# 08_SOM_USB_CARD.net
KiCad netlist of a schematic drawn in Altium Designer
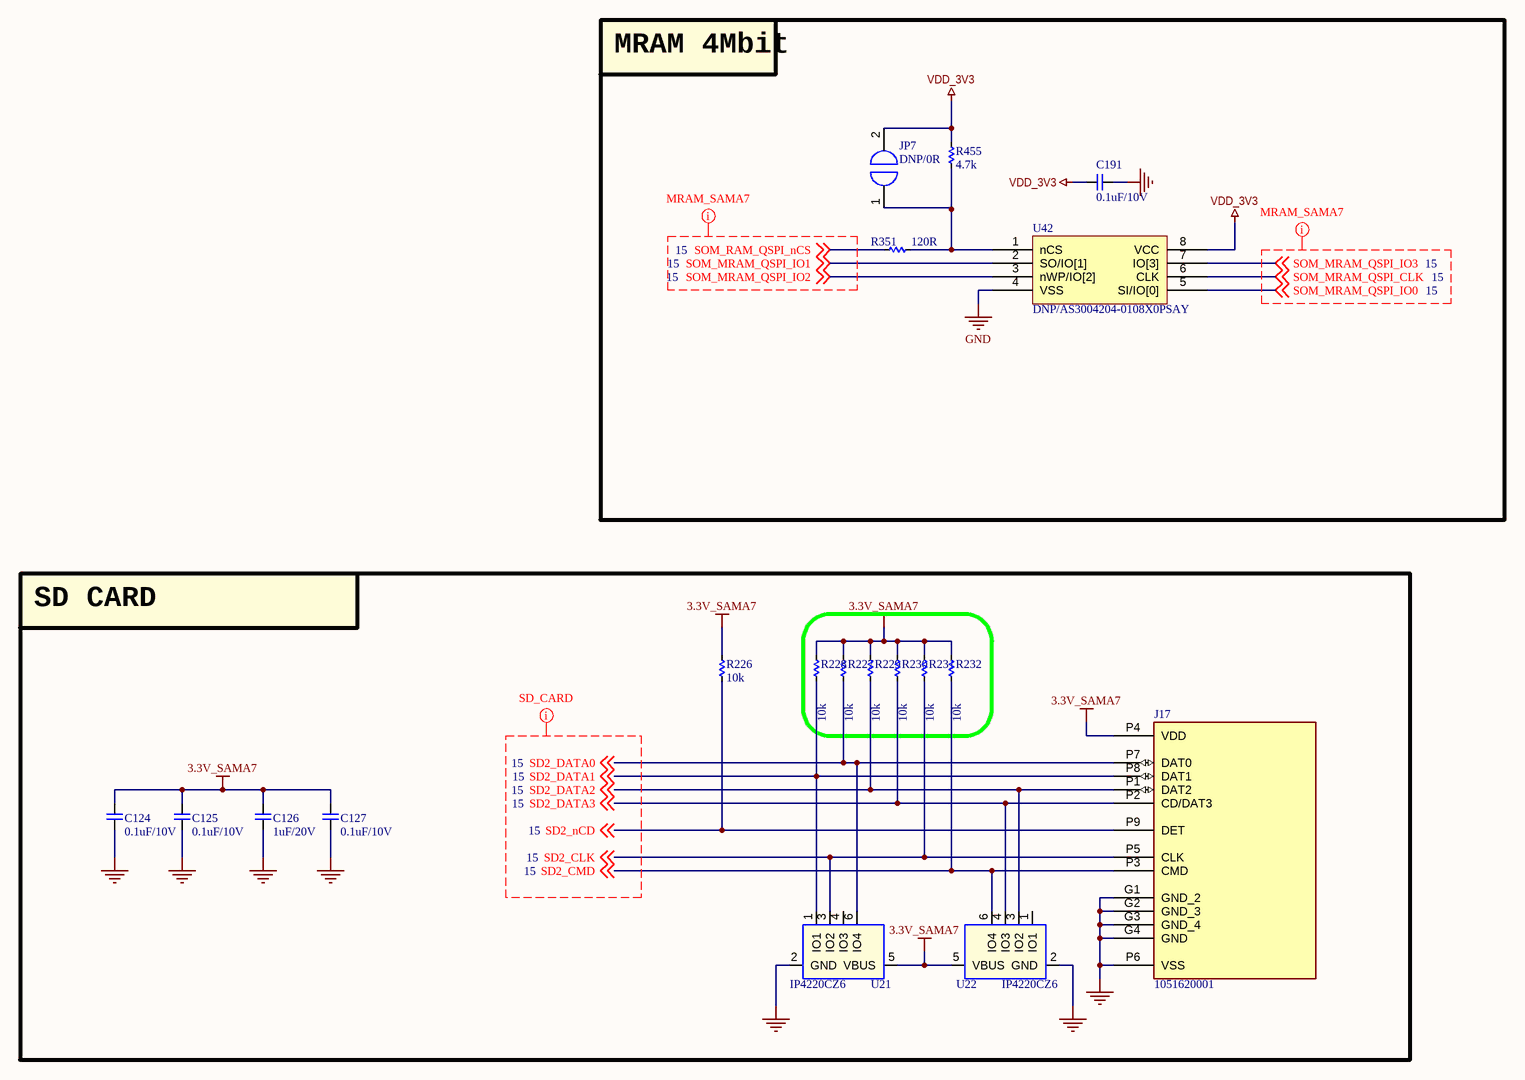
[diagram p0: 08_SOM_USB_CARD.SchDoc]

(export (version "E")
  (design (tool "Eeschema 10.0.6"))
  (components
    (comp (ref "C124")
      (value "0.1uF/10V")
      (footprint "CAP_C_1005X60")
      (description "CAP")
      (libsource (lib "LABLIB") (part "_CAP_C_2"))
    )
    (comp (ref "C125")
      (value "0.1uF/10V")
      (footprint "CAP_C_1005X60")
      (description "CAP")
      (libsource (lib "LABLIB") (part "_CAP_C_2"))
    )
    (comp (ref "C126")
      (value "1uF/20V")
      (footprint "CAP_C_1005X60")
      (description "CAP")
      (libsource (lib "LABLIB") (part "_CAP_C_2"))
    )
    (comp (ref "C127")
      (value "0.1uF/10V")
      (footprint "CAP_C_1005X60")
      (description "CAP")
      (libsource (lib "LABLIB") (part "_CAP_C_2"))
    )
    (comp (ref "C191")
      (value "0.1uF/10V")
      (footprint "CAP_C_1005X60")
      (description "CAP")
      (libsource (lib "LABLIB") (part "_CAP_C_2"))
    )
    (comp (ref "J17")
      (value "1051620001")
      (footprint "Molex_1051620001")
      (description "9 (8 + 1) Position Card Connector Secure Digital - microSDâ„¢ Surface Mount, Right Angle Gold")
      (fields (field (name "MF") "Molex"))
      (libsource (lib "new_component") (part "Molex_1051620001"))
    )
    (comp (ref "JP7") (value "DNP/0R") (footprint "JUMPER_1608") (libsource (lib "EXP_V1") (part "JUMPER")))
    (comp (ref "R226")
      (value "10k")
      (footprint "RES_C_1005X40")
      (description "RES")
      (libsource (lib "LABLIB") (part "_RES_B_2"))
    )
    (comp (ref "R227")
      (value "10k")
      (footprint "RES_C_1005X40")
      (description "RES")
      (libsource (lib "LABLIB") (part "_RES_B_2"))
    )
    (comp (ref "R228")
      (value "10k")
      (footprint "RES_C_1005X40")
      (description "RES")
      (libsource (lib "LABLIB") (part "_RES_B_2"))
    )
    (comp (ref "R229")
      (value "10k")
      (footprint "RES_C_1005X40")
      (description "RES")
      (libsource (lib "LABLIB") (part "_RES_B_2"))
    )
    (comp (ref "R230")
      (value "10k")
      (footprint "RES_C_1005X40")
      (description "RES")
      (libsource (lib "LABLIB") (part "_RES_B_2"))
    )
    (comp (ref "R231")
      (value "10k")
      (footprint "RES_C_1005X40")
      (description "RES")
      (libsource (lib "LABLIB") (part "_RES_B_2"))
    )
    (comp (ref "R232")
      (value "10k")
      (footprint "RES_C_1005X40")
      (description "RES")
      (libsource (lib "LABLIB") (part "_RES_B_2"))
    )
    (comp (ref "R351")
      (value "120R")
      (footprint "RES_C_1005X40")
      (description "RES")
      (libsource (lib "LABLIB") (part "_RES_B_2"))
    )
    (comp (ref "R455")
      (value "4.7k")
      (footprint "RES_C_1005X40")
      (description "RES")
      (libsource (lib "LABLIB") (part "_RES_B_2"))
    )
    (comp (ref "U21")
      (value "IP4220CZ6")
      (footprint "SOT95P280X145-6N")
      (libsource (lib "LABLIB") (part "IP4220CZ6_0"))
    )
    (comp (ref "U22")
      (value "IP4220CZ6")
      (footprint "SOT95P280X145-6N")
      (libsource (lib "") (part "IP4220CZ6_0_1"))
    )
    (comp (ref "U42")
      (value "DNP/AS3004204-0108X0PSAY")
      (footprint "SOIC127P790X216-8")
      (libsource (lib "LABLIB") (part "IC_RAM_AS3004204-0108X0PSAY"))
    )
  )
  (nets
    (net (code "1") (name "3.3V_SAMA7") (class "Default")
      (node (ref "C124") (pin "2") (pinfunction "2_2") (pintype "passive"))
      (node (ref "C125") (pin "2") (pinfunction "2_2") (pintype "passive"))
      (node (ref "C126") (pin "2") (pinfunction "2_2") (pintype "passive"))
      (node (ref "C127") (pin "2") (pinfunction "2_2") (pintype "passive"))
      (node (ref "J17") (pin "P4") (pinfunction "VDD_P4") (pintype "power_in"))
      (node (ref "R226") (pin "2") (pinfunction "2_2") (pintype "passive"))
      (node (ref "R227") (pin "2") (pinfunction "2_2") (pintype "passive"))
      (node (ref "R228") (pin "2") (pinfunction "2_2") (pintype "passive"))
      (node (ref "R229") (pin "2") (pinfunction "2_2") (pintype "passive"))
      (node (ref "R230") (pin "2") (pinfunction "2_2") (pintype "passive"))
      (node (ref "R231") (pin "2") (pinfunction "2_2") (pintype "passive"))
      (node (ref "R232") (pin "2") (pinfunction "2_2") (pintype "passive"))
      (node (ref "U21") (pin "5") (pinfunction "VBUS_5") (pintype "passive"))
      (node (ref "U22") (pin "5") (pinfunction "VBUS_5") (pintype "passive"))
    )
    (net (code "2") (name "GND") (class "Default")
      (node (ref "C124") (pin "1") (pinfunction "1_1") (pintype "passive"))
      (node (ref "C125") (pin "1") (pinfunction "1_1") (pintype "passive"))
      (node (ref "C126") (pin "1") (pinfunction "1_1") (pintype "passive"))
      (node (ref "C127") (pin "1") (pinfunction "1_1") (pintype "passive"))
      (node (ref "C191") (pin "1") (pinfunction "1_1") (pintype "passive"))
      (node (ref "J17") (pin "G1") (pinfunction "GND_2_G1") (pintype "passive"))
      (node (ref "J17") (pin "G2") (pinfunction "GND_3_G2") (pintype "passive"))
      (node (ref "J17") (pin "G3") (pinfunction "GND_4_G3") (pintype "passive"))
      (node (ref "J17") (pin "G4") (pinfunction "GND_G4") (pintype "passive"))
      (node (ref "J17") (pin "P6") (pinfunction "VSS_P6") (pintype "passive"))
      (node (ref "U21") (pin "2") (pinfunction "GND_2") (pintype "passive"))
      (node (ref "U22") (pin "2") (pinfunction "GND_2") (pintype "passive"))
      (node (ref "U42") (pin "4") (pinfunction "VSS_4") (pintype "passive"))
    )
    (net (code "3") (name "Net-(U42-nCS)") (class "Default")
      (node (ref "JP7") (pin "1") (pinfunction "1_1") (pintype "passive"))
      (node (ref "R351") (pin "1") (pinfunction "1_1") (pintype "passive"))
      (node (ref "R455") (pin "1") (pinfunction "1_1") (pintype "passive"))
      (node (ref "U42") (pin "1") (pinfunction "nCS_1") (pintype "passive"))
    )
    (net (code "4") (name "SD2_CLK") (class "Default")
      (node (ref "J17") (pin "P5") (pinfunction "CLK_P5") (pintype "passive"))
      (node (ref "R231") (pin "1") (pinfunction "1_1") (pintype "passive"))
      (node (ref "U21") (pin "3") (pinfunction "IO2_3") (pintype "passive"))
    )
    (net (code "5") (name "SD2_CMD") (class "Default")
      (node (ref "J17") (pin "P3") (pinfunction "CMD_P3") (pintype "passive"))
      (node (ref "R232") (pin "1") (pinfunction "1_1") (pintype "passive"))
      (node (ref "U22") (pin "6") (pinfunction "IO4_6") (pintype "passive"))
    )
    (net (code "6") (name "SD2_DATA0") (class "Default")
      (node (ref "J17") (pin "P7") (pinfunction "DAT0_P7") (pintype "bidirectional"))
      (node (ref "R227") (pin "1") (pinfunction "1_1") (pintype "passive"))
      (node (ref "U21") (pin "6") (pinfunction "IO4_6") (pintype "passive"))
    )
    (net (code "7") (name "SD2_DATA1") (class "Default")
      (node (ref "J17") (pin "P8") (pinfunction "DAT1_P8") (pintype "bidirectional"))
      (node (ref "R228") (pin "1") (pinfunction "1_1") (pintype "passive"))
      (node (ref "U21") (pin "1") (pinfunction "IO1_1") (pintype "passive"))
    )
    (net (code "8") (name "SD2_DATA2") (class "Default")
      (node (ref "J17") (pin "P1") (pinfunction "DAT2_P1") (pintype "bidirectional"))
      (node (ref "R229") (pin "1") (pinfunction "1_1") (pintype "passive"))
      (node (ref "U22") (pin "3") (pinfunction "IO2_3") (pintype "passive"))
    )
    (net (code "9") (name "SD2_DATA3") (class "Default")
      (node (ref "J17") (pin "P2") (pinfunction "CD/DAT3_P2") (pintype "passive"))
      (node (ref "R230") (pin "1") (pinfunction "1_1") (pintype "passive"))
      (node (ref "U22") (pin "4") (pinfunction "IO3_4") (pintype "passive"))
    )
    (net (code "10") (name "SD2_nCD") (class "Default")
      (node (ref "J17") (pin "P9") (pinfunction "DET_P9") (pintype "passive"))
      (node (ref "R226") (pin "1") (pinfunction "1_1") (pintype "passive"))
    )
    (net (code "11") (name "SOM_MRAM_QSPI_CLK") (class "Default")
      (node (ref "U42") (pin "6") (pinfunction "CLK_6") (pintype "passive"))
    )
    (net (code "12") (name "SOM_MRAM_QSPI_IO0") (class "Default")
      (node (ref "U42") (pin "5") (pinfunction "SI/IO[0]_5") (pintype "passive"))
    )
    (net (code "13") (name "SOM_MRAM_QSPI_IO1") (class "Default")
      (node (ref "U42") (pin "2") (pinfunction "SO/IO[1]_2") (pintype "passive"))
    )
    (net (code "14") (name "SOM_MRAM_QSPI_IO2") (class "Default")
      (node (ref "U42") (pin "3") (pinfunction "nWP/IO[2]_3") (pintype "passive"))
    )
    (net (code "15") (name "SOM_MRAM_QSPI_IO3") (class "Default")
      (node (ref "U42") (pin "7") (pinfunction "IO[3]_7") (pintype "passive"))
    )
    (net (code "16") (name "SOM_RAM_QSPI_nCS") (class "Default")
      (node (ref "R351") (pin "2") (pinfunction "2_2") (pintype "passive"))
    )
    (net (code "17") (name "VDD_3V3") (class "Default")
      (node (ref "C191") (pin "2") (pinfunction "2_2") (pintype "passive"))
      (node (ref "JP7") (pin "2") (pinfunction "2_2") (pintype "passive"))
      (node (ref "R455") (pin "2") (pinfunction "2_2") (pintype "passive"))
      (node (ref "U42") (pin "8") (pinfunction "VCC_8") (pintype "passive"))
    )
    (net (code "18") (name "unconnected-(U21-IO3-Pad4)") (class "Default")
      (node (ref "U21") (pin "4") (pinfunction "IO3_4") (pintype "passive"))
    )
    (net (code "19") (name "unconnected-(U22-IO1-Pad1)") (class "Default")
      (node (ref "U22") (pin "1") (pinfunction "IO1_1") (pintype "passive"))
    )
  )
)
